# untitled.net
KiCad netlist of a schematic drawn in EAGLE
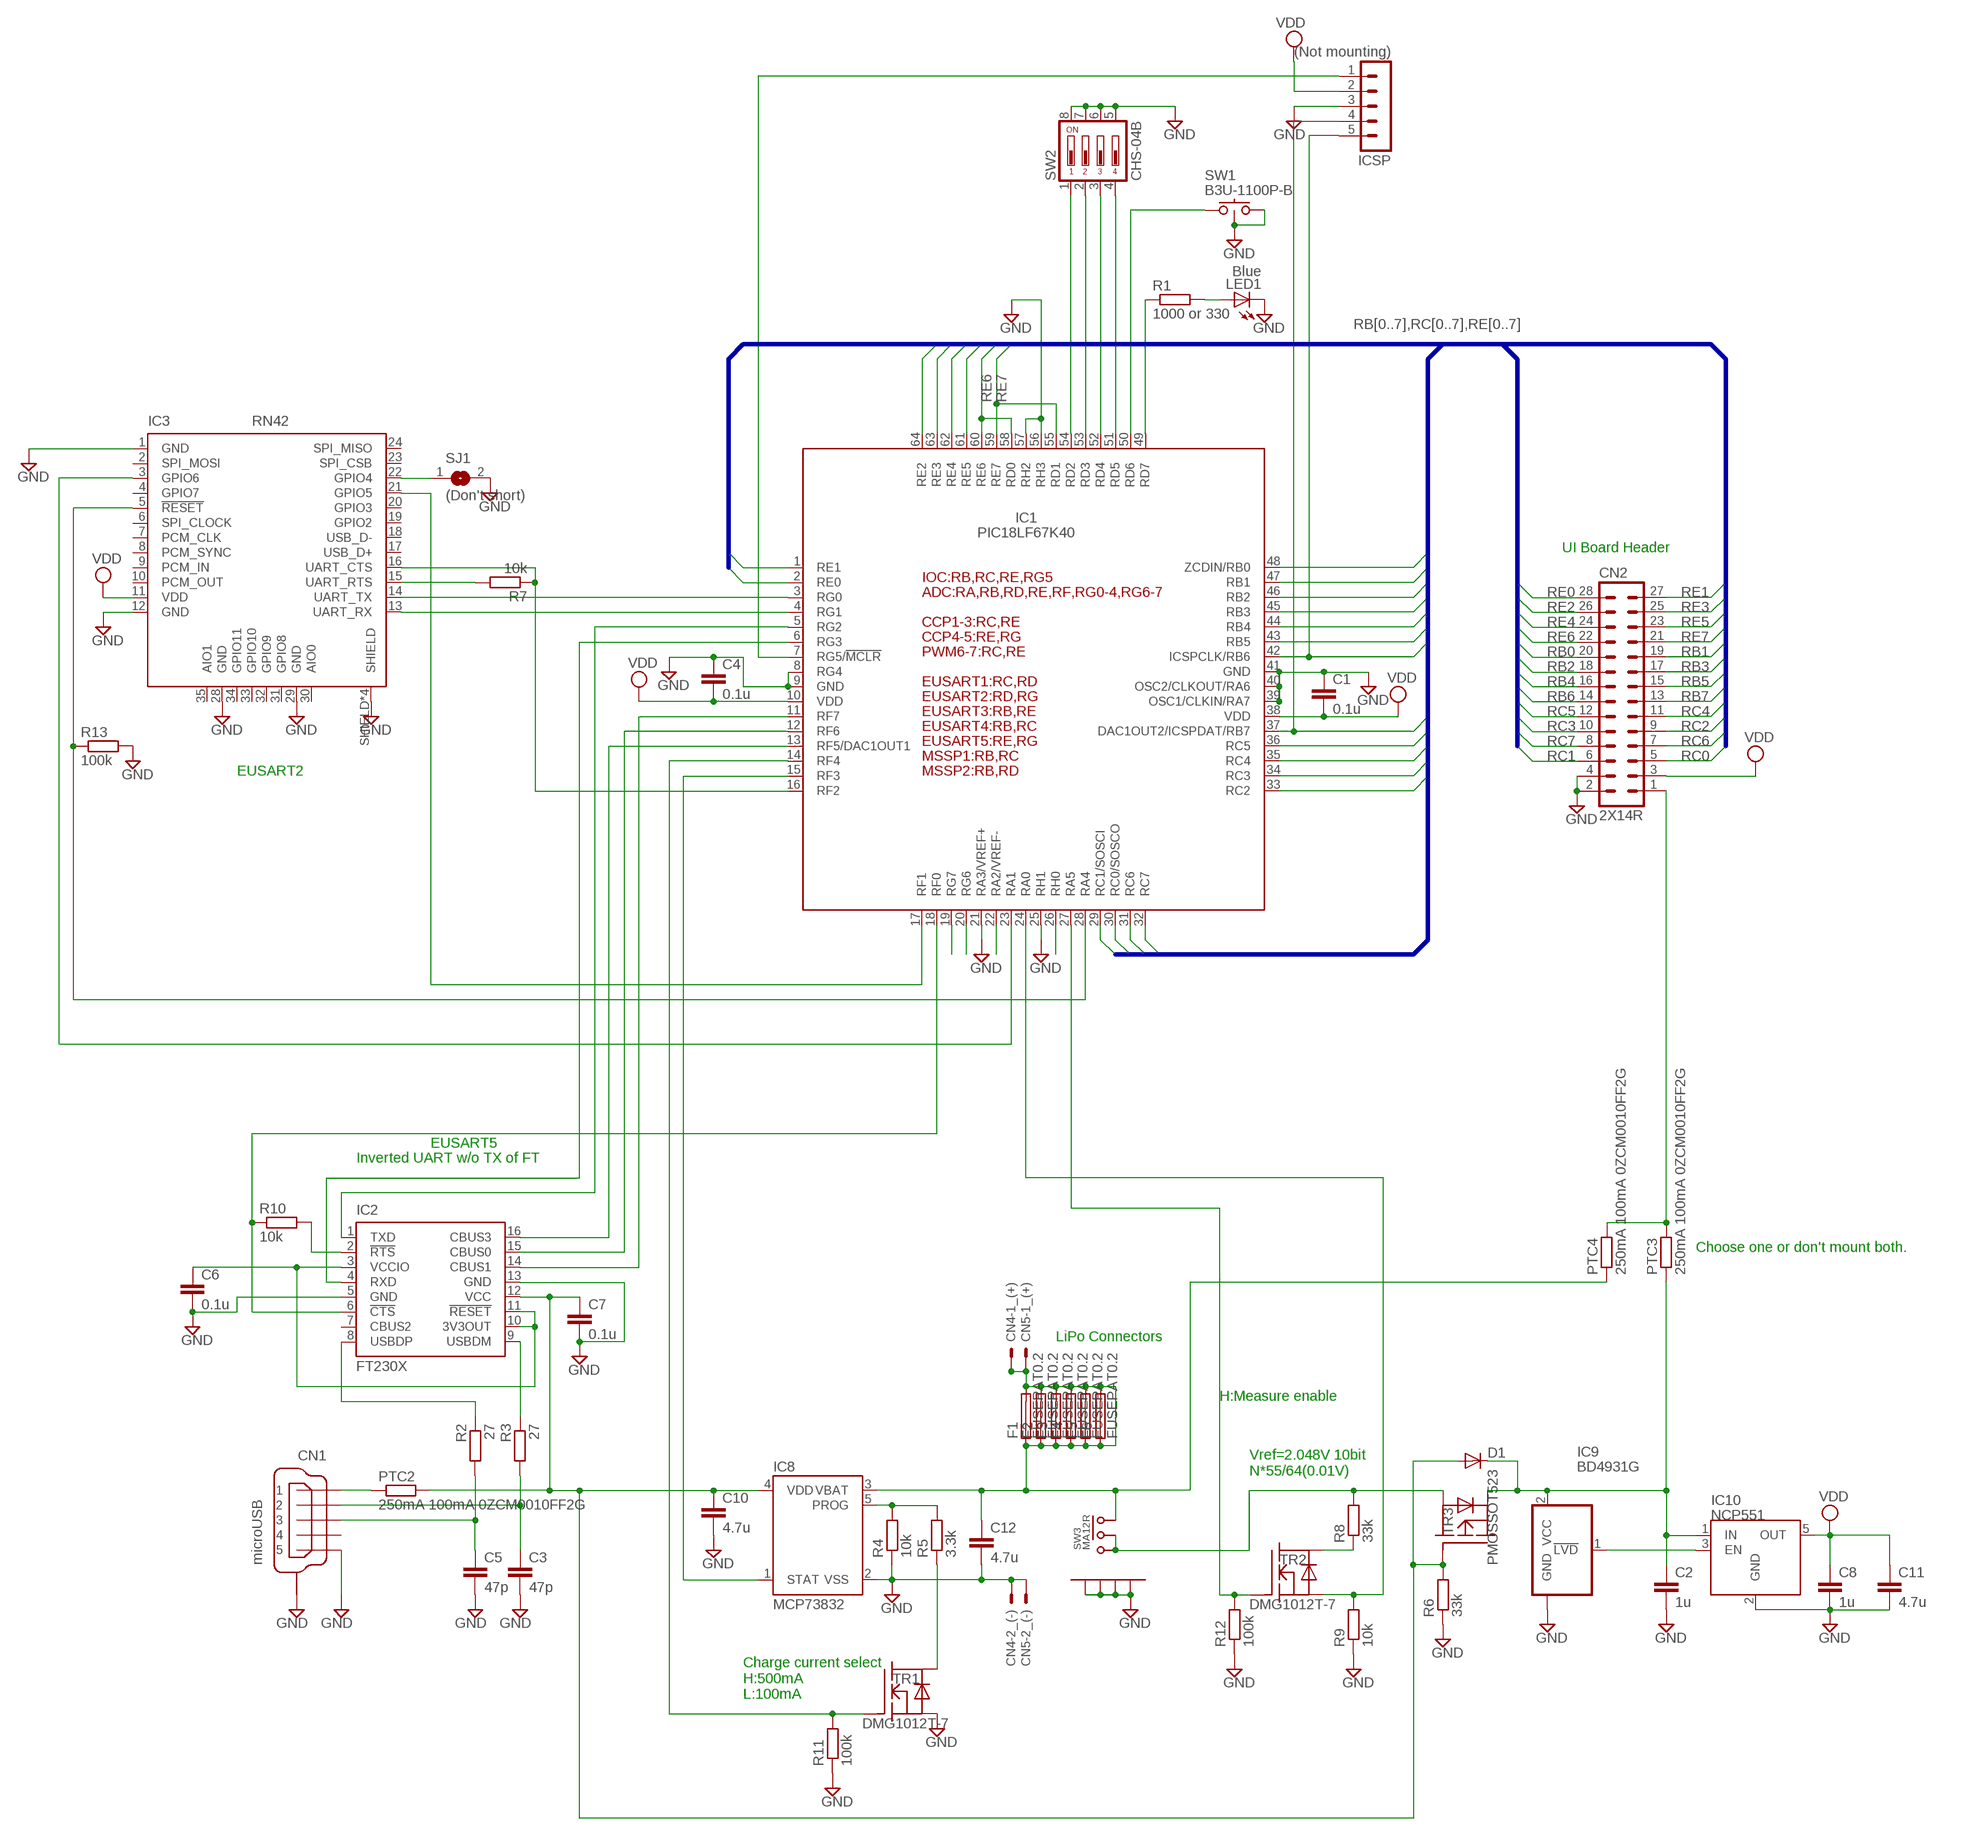
[diagram p0: schematic, sheet 1]

(export (version "E")
  (design (tool "Eeschema 10.0.6"))
  (components
    (comp (ref "C1")
      (value "0.1u")
      (footprint "eagle-import:C0402-SS")
      (libsource (lib "eagle-import") (part "C-EUC0402-SS"))
    )
    (comp (ref "C2")
      (value "1u")
      (footprint "eagle-import:C0805")
      (libsource (lib "eagle-import") (part "C-EUC0805"))
    )
    (comp (ref "C3")
      (value "47p")
      (footprint "eagle-import:C0402-SS")
      (libsource (lib "eagle-import") (part "C-EUC0402-SS"))
    )
    (comp (ref "C4")
      (value "0.1u")
      (footprint "eagle-import:C0402-SS")
      (libsource (lib "eagle-import") (part "C-EUC0402-SS"))
    )
    (comp (ref "C5")
      (value "47p")
      (footprint "eagle-import:C0402-SS")
      (libsource (lib "eagle-import") (part "C-EUC0402-SS"))
    )
    (comp (ref "C6")
      (value "0.1u")
      (footprint "eagle-import:C0402-SS")
      (libsource (lib "eagle-import") (part "C-EUC0402-SS"))
    )
    (comp (ref "C7")
      (value "0.1u")
      (footprint "eagle-import:C0402-SS")
      (libsource (lib "eagle-import") (part "C-EUC0402-SS"))
    )
    (comp (ref "C8")
      (value "1u")
      (footprint "eagle-import:C0805")
      (libsource (lib "eagle-import") (part "C-EUC0805"))
    )
    (comp (ref "C10")
      (value "4.7u")
      (footprint "eagle-import:C0805")
      (libsource (lib "eagle-import") (part "C-EUC0805"))
    )
    (comp (ref "C11")
      (value "4.7u")
      (footprint "eagle-import:C0805")
      (libsource (lib "eagle-import") (part "C-EUC0805"))
    )
    (comp (ref "C12")
      (value "4.7u")
      (footprint "eagle-import:C0805")
      (libsource (lib "eagle-import") (part "C-EUC0805"))
    )
    (comp (ref "CN1")
      (value "microUSB")
      (footprint "eagle-import:10118194-0001LF")
      (libsource (lib "eagle-import") (part "MICROUSB(10118194-0001LF)"))
    )
    (comp (ref "CN2")
      (value "2X14R")
      (footprint "eagle-import:2MM_14X2_R")
      (libsource (lib "eagle-import") (part "2X14R"))
    )
    (comp (ref "CN4")
      (value "2P_(POWER)PH_S")
      (footprint "eagle-import:PH-2_S")
      (libsource (lib "eagle-import") (part "2P_(POWER)PH_S"))
    )
    (comp (ref "CN5")
      (value "2P_(POWER)PH_S")
      (footprint "eagle-import:PH-2_S")
      (libsource (lib "eagle-import") (part "2P_(POWER)PH_S"))
    )
    (comp (ref "D1")
      (value "DIODE-VMN2")
      (footprint "eagle-import:VMN2")
      (libsource (lib "eagle-import") (part "DIODE-VMN2"))
    )
    (comp (ref "F1")
      (value "FUSEPAT0.2")
      (footprint "eagle-import:FUSE_PAT1")
      (libsource (lib "eagle-import") (part "FUSEPAT0.2"))
    )
    (comp (ref "F2")
      (value "FUSEPAT0.2")
      (footprint "eagle-import:FUSE_PAT1")
      (libsource (lib "eagle-import") (part "FUSEPAT0.2"))
    )
    (comp (ref "F3")
      (value "FUSEPAT0.2")
      (footprint "eagle-import:FUSE_PAT1")
      (libsource (lib "eagle-import") (part "FUSEPAT0.2"))
    )
    (comp (ref "F4")
      (value "FUSEPAT0.2")
      (footprint "eagle-import:FUSE_PAT1")
      (libsource (lib "eagle-import") (part "FUSEPAT0.2"))
    )
    (comp (ref "F5")
      (value "FUSEPAT0.2")
      (footprint "eagle-import:FUSE_PAT1")
      (libsource (lib "eagle-import") (part "FUSEPAT0.2"))
    )
    (comp (ref "F6")
      (value "FUSEPAT0.2")
      (footprint "eagle-import:FUSE_PAT1")
      (libsource (lib "eagle-import") (part "FUSEPAT0.2"))
    )
    (comp (ref "IC1")
      (value "PIC18LF67K40")
      (footprint "eagle-import:TQFP64-10X10")
      (libsource (lib "eagle-import") (part "PIC18F67K40"))
    )
    (comp (ref "IC2")
      (value "FT230X")
      (footprint "eagle-import:SSOP16")
      (libsource (lib "eagle-import") (part "FT230XS"))
    )
    (comp (ref "IC3")
      (value "RN42")
      (footprint "eagle-import:RN-42")
      (libsource (lib "eagle-import") (part "RN-42"))
    )
    (comp (ref "IC8")
      (value "MCP73832")
      (footprint "eagle-import:SOT23-5L")
      (libsource (lib "eagle-import") (part "MCP73831"))
    )
    (comp (ref "IC9")
      (value "BD4931G")
      (footprint "eagle-import:SOT23-5L")
      (libsource (lib "eagle-import") (part "BD48XX"))
    )
    (comp (ref "IC10")
      (value "NCP551")
      (footprint "eagle-import:SOT23-5L")
      (libsource (lib "eagle-import") (part "NCP551"))
    )
    (comp (ref "ICSP")
      (value "(Not mounting)")
      (footprint "eagle-import:MA05-1")
      (libsource (lib "eagle-import") (part "MA05-1"))
    )
    (comp (ref "LED1")
      (value "Blue")
      (footprint "eagle-import:CHIP-LED1005")
      (libsource (lib "eagle-import") (part "LED1005"))
    )
    (comp (ref "PTC2")
      (value "250mA 100mA 0ZCM0010FF2G")
      (footprint "eagle-import:R0603")
      (libsource (lib "eagle-import") (part "R-EU_R0603"))
    )
    (comp (ref "PTC3")
      (value "250mA 100mA 0ZCM0010FF2G")
      (footprint "eagle-import:R0603")
      (libsource (lib "eagle-import") (part "R-EU_R0603"))
    )
    (comp (ref "PTC4")
      (value "250mA 100mA 0ZCM0010FF2G")
      (footprint "eagle-import:R0603")
      (libsource (lib "eagle-import") (part "R-EU_R0603"))
    )
    (comp (ref "R1")
      (value "1000 or 330")
      (footprint "eagle-import:R0402-SS")
      (libsource (lib "eagle-import") (part "R-EU_R0402-SS"))
    )
    (comp (ref "R2")
      (value "27")
      (footprint "eagle-import:R0402-SS")
      (libsource (lib "eagle-import") (part "R-EU_R0402-SS"))
    )
    (comp (ref "R3")
      (value "27")
      (footprint "eagle-import:R0402-SS")
      (libsource (lib "eagle-import") (part "R-EU_R0402-SS"))
    )
    (comp (ref "R4")
      (value "10k")
      (footprint "eagle-import:R0402-SS")
      (libsource (lib "eagle-import") (part "R-EU_R0402-SS"))
    )
    (comp (ref "R5")
      (value "3.3k")
      (footprint "eagle-import:R0402-SS")
      (libsource (lib "eagle-import") (part "R-EU_R0402-SS"))
    )
    (comp (ref "R6")
      (value "33k")
      (footprint "eagle-import:R0402-SS")
      (libsource (lib "eagle-import") (part "R-EU_R0402-SS"))
    )
    (comp (ref "R7")
      (value "10k")
      (footprint "eagle-import:R0402-SS")
      (libsource (lib "eagle-import") (part "R-EU_R0402-SS"))
    )
    (comp (ref "R8")
      (value "33k")
      (footprint "eagle-import:R0402-SS")
      (libsource (lib "eagle-import") (part "R-EU_R0402-SS"))
    )
    (comp (ref "R9")
      (value "10k")
      (footprint "eagle-import:R0402-SS")
      (libsource (lib "eagle-import") (part "R-EU_R0402-SS"))
    )
    (comp (ref "R10")
      (value "10k")
      (footprint "eagle-import:R0402-SS")
      (libsource (lib "eagle-import") (part "R-EU_R0402-SS"))
    )
    (comp (ref "R11")
      (value "100k")
      (footprint "eagle-import:R0402-SS")
      (libsource (lib "eagle-import") (part "R-EU_R0402-SS"))
    )
    (comp (ref "R12")
      (value "100k")
      (footprint "eagle-import:R0402-SS")
      (libsource (lib "eagle-import") (part "R-EU_R0402-SS"))
    )
    (comp (ref "R13")
      (value "100k")
      (footprint "eagle-import:R0402-SS")
      (libsource (lib "eagle-import") (part "R-EU_R0402-SS"))
    )
    (comp (ref "SJ1")
      (value "(Don't short)")
      (footprint "eagle-import:SJ")
      (libsource (lib "eagle-import") (part "SJ"))
    )
    (comp (ref "SW1")
      (value "B3U-1100P-B")
      (footprint "eagle-import:B3U-1100P-B")
      (libsource (lib "eagle-import") (part "SW_WITH_EARTH(B3U-1100P)"))
    )
    (comp (ref "SW2")
      (value "CHS-04B")
      (footprint "eagle-import:CHS-04B")
      (libsource (lib "eagle-import") (part "CHS-04B"))
    )
    (comp (ref "SW3")
      (value "MA12R")
      (footprint "eagle-import:MA12R")
      (libsource (lib "eagle-import") (part "MA12R"))
    )
    (comp (ref "TR1")
      (value "DMG1012T-7")
      (footprint "eagle-import:SOT523")
      (libsource (lib "eagle-import") (part "NMOSSOT523"))
    )
    (comp (ref "TR2")
      (value "DMG1012T-7")
      (footprint "eagle-import:SOT523")
      (libsource (lib "eagle-import") (part "NMOSSOT523"))
    )
    (comp (ref "TR3")
      (value "PMOSSOT523")
      (footprint "eagle-import:SOT523")
      (libsource (lib "eagle-import") (part "PMOSSOT523"))
    )
  )
  (nets
    (net (code "1") (name "/RB0") (class "Default")
      (node (ref "CN2") (pin "20") (pinfunction "20_20") (pintype "passive"))
      (node (ref "IC1") (pin "48") (pinfunction "ZCDIN/RB0_48") (pintype "bidirectional"))
    )
    (net (code "2") (name "/RB1") (class "Default")
      (node (ref "CN2") (pin "19") (pinfunction "19_19") (pintype "passive"))
      (node (ref "IC1") (pin "47") (pinfunction "RB1_47") (pintype "bidirectional"))
    )
    (net (code "3") (name "/RB2") (class "Default")
      (node (ref "CN2") (pin "18") (pinfunction "18_18") (pintype "passive"))
      (node (ref "IC1") (pin "46") (pinfunction "RB2_46") (pintype "bidirectional"))
    )
    (net (code "4") (name "/RB3") (class "Default")
      (node (ref "CN2") (pin "17") (pinfunction "17_17") (pintype "passive"))
      (node (ref "IC1") (pin "45") (pinfunction "RB3_45") (pintype "bidirectional"))
    )
    (net (code "5") (name "/RB4") (class "Default")
      (node (ref "CN2") (pin "16") (pinfunction "16_16") (pintype "passive"))
      (node (ref "IC1") (pin "44") (pinfunction "RB4_44") (pintype "bidirectional"))
    )
    (net (code "6") (name "/RB5") (class "Default")
      (node (ref "CN2") (pin "15") (pinfunction "15_15") (pintype "passive"))
      (node (ref "IC1") (pin "43") (pinfunction "RB5_43") (pintype "bidirectional"))
    )
    (net (code "7") (name "/RB6") (class "Default")
      (node (ref "CN2") (pin "14") (pinfunction "14_14") (pintype "passive"))
      (node (ref "IC1") (pin "42") (pinfunction "ICSPCLK/RB6_42") (pintype "bidirectional"))
      (node (ref "ICSP") (pin "5") (pinfunction "5_5") (pintype "passive"))
    )
    (net (code "8") (name "/RB7") (class "Default")
      (node (ref "CN2") (pin "13") (pinfunction "13_13") (pintype "passive"))
      (node (ref "IC1") (pin "37") (pinfunction "DAC1OUT2/ICSPDAT/RB7_37") (pintype "bidirectional"))
      (node (ref "ICSP") (pin "4") (pinfunction "4_4") (pintype "passive"))
    )
    (net (code "9") (name "/RC0") (class "Default")
      (node (ref "CN2") (pin "5") (pinfunction "5_5") (pintype "passive"))
      (node (ref "IC1") (pin "30") (pinfunction "RC0/SOSCO_30") (pintype "bidirectional"))
    )
    (net (code "10") (name "/RC1") (class "Default")
      (node (ref "CN2") (pin "6") (pinfunction "6_6") (pintype "passive"))
      (node (ref "IC1") (pin "29") (pinfunction "RC1/SOSCI_29") (pintype "bidirectional"))
    )
    (net (code "11") (name "/RC2") (class "Default")
      (node (ref "CN2") (pin "9") (pinfunction "9_9") (pintype "passive"))
      (node (ref "IC1") (pin "33") (pinfunction "RC2_33") (pintype "bidirectional"))
    )
    (net (code "12") (name "/RC3") (class "Default")
      (node (ref "CN2") (pin "10") (pinfunction "10_10") (pintype "passive"))
      (node (ref "IC1") (pin "34") (pinfunction "RC3_34") (pintype "bidirectional"))
    )
    (net (code "13") (name "/RC4") (class "Default")
      (node (ref "CN2") (pin "11") (pinfunction "11_11") (pintype "passive"))
      (node (ref "IC1") (pin "35") (pinfunction "RC4_35") (pintype "bidirectional"))
    )
    (net (code "14") (name "/RC5") (class "Default")
      (node (ref "CN2") (pin "12") (pinfunction "12_12") (pintype "passive"))
      (node (ref "IC1") (pin "36") (pinfunction "RC5_36") (pintype "bidirectional"))
    )
    (net (code "15") (name "/RC6") (class "Default")
      (node (ref "CN2") (pin "7") (pinfunction "7_7") (pintype "passive"))
      (node (ref "IC1") (pin "31") (pinfunction "RC6_31") (pintype "bidirectional"))
    )
    (net (code "16") (name "/RC7") (class "Default")
      (node (ref "CN2") (pin "8") (pinfunction "8_8") (pintype "passive"))
      (node (ref "IC1") (pin "32") (pinfunction "RC7_32") (pintype "bidirectional"))
    )
    (net (code "17") (name "/RE0") (class "Default")
      (node (ref "CN2") (pin "28") (pinfunction "28_28") (pintype "passive"))
      (node (ref "IC1") (pin "2") (pinfunction "RE0_2") (pintype "bidirectional"))
    )
    (net (code "18") (name "/RE1") (class "Default")
      (node (ref "CN2") (pin "27") (pinfunction "27_27") (pintype "passive"))
      (node (ref "IC1") (pin "1") (pinfunction "RE1_1") (pintype "bidirectional"))
    )
    (net (code "19") (name "/RE2") (class "Default")
      (node (ref "CN2") (pin "26") (pinfunction "26_26") (pintype "passive"))
      (node (ref "IC1") (pin "64") (pinfunction "RE2_64") (pintype "bidirectional"))
    )
    (net (code "20") (name "/RE3") (class "Default")
      (node (ref "CN2") (pin "25") (pinfunction "25_25") (pintype "passive"))
      (node (ref "IC1") (pin "63") (pinfunction "RE3_63") (pintype "bidirectional"))
    )
    (net (code "21") (name "/RE4") (class "Default")
      (node (ref "CN2") (pin "24") (pinfunction "24_24") (pintype "passive"))
      (node (ref "IC1") (pin "62") (pinfunction "RE4_62") (pintype "bidirectional"))
    )
    (net (code "22") (name "/RE5") (class "Default")
      (node (ref "CN2") (pin "23") (pinfunction "23_23") (pintype "passive"))
      (node (ref "IC1") (pin "61") (pinfunction "RE5_61") (pintype "bidirectional"))
    )
    (net (code "23") (name "/RE6") (class "Default")
      (node (ref "CN2") (pin "22") (pinfunction "22_22") (pintype "passive"))
      (node (ref "IC1") (pin "58") (pinfunction "RD0_58") (pintype "bidirectional"))
      (node (ref "IC1") (pin "60") (pinfunction "RE6_60") (pintype "bidirectional"))
    )
    (net (code "24") (name "/RE7") (class "Default")
      (node (ref "CN2") (pin "21") (pinfunction "21_21") (pintype "passive"))
      (node (ref "IC1") (pin "55") (pinfunction "RD1_55") (pintype "bidirectional"))
      (node (ref "IC1") (pin "59") (pinfunction "RE7_59") (pintype "bidirectional"))
    )
    (net (code "26") (name "GND") (class "Default")
      (node (ref "C1") (pin "1") (pinfunction "1_1") (pintype "passive"))
      (node (ref "C10") (pin "2") (pinfunction "2_2") (pintype "passive"))
      (node (ref "C11") (pin "2") (pinfunction "2_2") (pintype "passive"))
      (node (ref "C12") (pin "2") (pinfunction "2_2") (pintype "passive"))
      (node (ref "C2") (pin "2") (pinfunction "2_2") (pintype "passive"))
      (node (ref "C3") (pin "2") (pinfunction "2_2") (pintype "passive"))
      (node (ref "C4") (pin "1") (pinfunction "1_1") (pintype "passive"))
      (node (ref "C5") (pin "2") (pinfunction "2_2") (pintype "passive"))
      (node (ref "C6") (pin "2") (pinfunction "2_2") (pintype "passive"))
      (node (ref "C7") (pin "2") (pinfunction "2_2") (pintype "passive"))
      (node (ref "C8") (pin "2") (pinfunction "2_2") (pintype "passive"))
      (node (ref "CN1") (pin "P$5") (pinfunction "5_P$5") (pintype "passive"))
      (node (ref "CN1") (pin "P$6") (pinfunction "S_P$6") (pintype "passive"))
      (node (ref "CN1") (pin "P$7") (pinfunction "S_P$7") (pintype "passive"))
      (node (ref "CN1") (pin "S1") (pinfunction "S_S1") (pintype "passive"))
      (node (ref "CN1") (pin "S10") (pinfunction "S_S10") (pintype "passive"))
      (node (ref "CN1") (pin "S2") (pinfunction "S_S2") (pintype "passive"))
      (node (ref "CN1") (pin "S3") (pinfunction "S_S3") (pintype "passive"))
      (node (ref "CN1") (pin "S4") (pinfunction "S_S4") (pintype "passive"))
      (node (ref "CN1") (pin "S5") (pinfunction "S_S5") (pintype "passive"))
      (node (ref "CN1") (pin "S6") (pinfunction "S_S6") (pintype "passive"))
      (node (ref "CN1") (pin "S7") (pinfunction "S_S7") (pintype "passive"))
      (node (ref "CN1") (pin "S8") (pinfunction "S_S8") (pintype "passive"))
      (node (ref "CN1") (pin "S9") (pinfunction "S_S9") (pintype "passive"))
      (node (ref "CN2") (pin "2") (pinfunction "2_2") (pintype "passive"))
      (node (ref "CN2") (pin "4") (pinfunction "4_4") (pintype "passive"))
      (node (ref "CN4") (pin "2") (pinfunction "S_2") (pintype "passive"))
      (node (ref "CN5") (pin "2") (pinfunction "S_2") (pintype "passive"))
      (node (ref "IC1") (pin "21") (pinfunction "RA3/VREF+_21") (pintype "bidirectional"))
      (node (ref "IC1") (pin "25") (pinfunction "RH1_25") (pintype "bidirectional"))
      (node (ref "IC1") (pin "39") (pinfunction "OSC1/CLKIN/RA7_39") (pintype "bidirectional"))
      (node (ref "IC1") (pin "40") (pinfunction "OSC2/CLKOUT/RA6_40") (pintype "bidirectional"))
      (node (ref "IC1") (pin "41") (pinfunction "GND_41") (pintype "power_in"))
      (node (ref "IC1") (pin "56") (pinfunction "RH3_56") (pintype "bidirectional"))
      (node (ref "IC1") (pin "57") (pinfunction "RH2_57") (pintype "bidirectional"))
      (node (ref "IC1") (pin "8") (pinfunction "RG4_8") (pintype "bidirectional"))
      (node (ref "IC1") (pin "9") (pinfunction "GND_9") (pintype "power_in"))
      (node (ref "IC10") (pin "2") (pinfunction "GND_2") (pintype "power_in"))
      (node (ref "IC2") (pin "13") (pinfunction "GND_13") (pintype "power_in"))
      (node (ref "IC2") (pin "5") (pinfunction "GND_5") (pintype "power_in"))
      (node (ref "IC3") (pin "1") (pinfunction "GND_1") (pintype "bidirectional"))
      (node (ref "IC3") (pin "12") (pinfunction "GND_12") (pintype "bidirectional"))
      (node (ref "IC3") (pin "28") (pinfunction "GND_28") (pintype "bidirectional"))
      (node (ref "IC3") (pin "29") (pinfunction "GND_29") (pintype "bidirectional"))
      (node (ref "IC3") (pin "SHIELD") (pinfunction "SHIELD_SHIELD") (pintype "bidirectional"))
      (node (ref "IC3") (pin "SHIELD@1") (pinfunction "SHIELD_SHIELD@1") (pintype "bidirectional"))
      (node (ref "IC3") (pin "SHIELD@2") (pinfunction "SHIELD_SHIELD@2") (pintype "bidirectional"))
      (node (ref "IC3") (pin "SHIELD@3") (pinfunction "SHIELD_SHIELD@3") (pintype "bidirectional"))
      (node (ref "IC8") (pin "2") (pinfunction "VSS_2") (pintype "power_in"))
      (node (ref "IC9") (pin "3") (pinfunction "GND_3") (pintype "power_in"))
      (node (ref "ICSP") (pin "3") (pinfunction "3_3") (pintype "passive"))
      (node (ref "LED1") (pin "C") (pinfunction "C_C") (pintype "passive"))
      (node (ref "R11") (pin "1") (pinfunction "1_1") (pintype "passive"))
      (node (ref "R12") (pin "1") (pinfunction "1_1") (pintype "passive"))
      (node (ref "R13") (pin "2") (pinfunction "2_2") (pintype "passive"))
      (node (ref "R4") (pin "1") (pinfunction "1_1") (pintype "passive"))
      (node (ref "R6") (pin "1") (pinfunction "1_1") (pintype "passive"))
      (node (ref "R9") (pin "1") (pinfunction "1_1") (pintype "passive"))
      (node (ref "SJ1") (pin "2") (pinfunction "2_2") (pintype "passive"))
      (node (ref "SW1") (pin "P$2") (pinfunction "P$2_P$2") (pintype "passive"))
      (node (ref "SW1") (pin "P$3") (pinfunction "P$3_P$3") (pintype "passive"))
      (node (ref "SW2") (pin "5") (pinfunction "5_5") (pintype "passive"))
      (node (ref "SW2") (pin "6") (pinfunction "6_6") (pintype "passive"))
      (node (ref "SW2") (pin "7") (pinfunction "7_7") (pintype "passive"))
      (node (ref "SW2") (pin "8") (pinfunction "8_8") (pintype "passive"))
      (node (ref "SW3") (pin "P$4") (pinfunction "P$1_P$4") (pintype "bidirectional"))
      (node (ref "SW3") (pin "P$5") (pinfunction "P$2_P$5") (pintype "bidirectional"))
      (node (ref "SW3") (pin "P$6") (pinfunction "P$3_P$6") (pintype "bidirectional"))
      (node (ref "SW3") (pin "P$7") (pinfunction "P$4_P$7") (pintype "bidirectional"))
      (node (ref "TR1") (pin "2") (pinfunction "S_2") (pintype "bidirectional"))
    )
    (net (code "27") (name "Net-(CN1-1)") (class "Default")
      (node (ref "CN1") (pin "P$1") (pinfunction "1_P$1") (pintype "passive"))
      (node (ref "PTC2") (pin "1") (pinfunction "1_1") (pintype "passive"))
    )
    (net (code "28") (name "Net-(CN1-2)") (class "Default")
      (node (ref "C3") (pin "1") (pinfunction "1_1") (pintype "passive"))
      (node (ref "CN1") (pin "P$2") (pinfunction "2_P$2") (pintype "passive"))
      (node (ref "R3") (pin "2") (pinfunction "2_2") (pintype "passive"))
    )
    (net (code "29") (name "Net-(CN1-3)") (class "Default")
      (node (ref "C5") (pin "1") (pinfunction "1_1") (pintype "passive"))
      (node (ref "CN1") (pin "P$3") (pinfunction "3_P$3") (pintype "passive"))
      (node (ref "R2") (pin "2") (pinfunction "2_2") (pintype "passive"))
    )
    (net (code "30") (name "Net-(CN2-Pad1)") (class "Default")
      (node (ref "CN2") (pin "1") (pinfunction "1_1") (pintype "passive"))
      (node (ref "PTC3") (pin "2") (pinfunction "2_2") (pintype "passive"))
      (node (ref "PTC4") (pin "2") (pinfunction "2_2") (pintype "passive"))
    )
    (net (code "31") (name "Net-(CN4A-S)") (class "Default")
      (node (ref "C12") (pin "1") (pinfunction "1_1") (pintype "passive"))
      (node (ref "CN4") (pin "1") (pinfunction "S_1") (pintype "passive"))
      (node (ref "CN5") (pin "1") (pinfunction "S_1") (pintype "passive"))
      (node (ref "F1") (pin "P$1") (pinfunction "1_P$1") (pintype "passive"))
      (node (ref "F1") (pin "P$2") (pinfunction "2_P$2") (pintype "passive"))
      (node (ref "F2") (pin "P$1") (pinfunction "1_P$1") (pintype "passive"))
      (node (ref "F2") (pin "P$2") (pinfunction "2_P$2") (pintype "passive"))
      (node (ref "F3") (pin "P$1") (pinfunction "1_P$1") (pintype "passive"))
      (node (ref "F3") (pin "P$2") (pinfunction "2_P$2") (pintype "passive"))
      (node (ref "F4") (pin "P$1") (pinfunction "1_P$1") (pintype "passive"))
      (node (ref "F4") (pin "P$2") (pinfunction "2_P$2") (pintype "passive"))
      (node (ref "F5") (pin "P$1") (pinfunction "1_P$1") (pintype "passive"))
      (node (ref "F5") (pin "P$2") (pinfunction "2_P$2") (pintype "passive"))
      (node (ref "F6") (pin "P$1") (pinfunction "1_P$1") (pintype "passive"))
      (node (ref "F6") (pin "P$2") (pinfunction "2_P$2") (pintype "passive"))
      (node (ref "IC8") (pin "3") (pinfunction "VBAT_3") (pintype "output"))
      (node (ref "PTC4") (pin "1") (pinfunction "1_1") (pintype "passive"))
      (node (ref "SW3") (pin "P$1") (pinfunction "1_P$1") (pintype "bidirectional"))
    )
    (net (code "32") (name "Net-(IC1-RA0)") (class "Default")
      (node (ref "IC1") (pin "24") (pinfunction "RA0_24") (pintype "bidirectional"))
      (node (ref "R9") (pin "2") (pinfunction "2_2") (pintype "passive"))
      (node (ref "TR2") (pin "2") (pinfunction "S_2") (pintype "bidirectional"))
    )
    (net (code "33") (name "Net-(IC1-RA1)") (class "Default")
      (node (ref "IC1") (pin "23") (pinfunction "RA1_23") (pintype "bidirectional"))
      (node (ref "IC3") (pin "3") (pinfunction "GPIO6_3") (pintype "bidirectional"))
    )
    (net (code "34") (name "Net-(IC1-RA4)") (class "Default")
      (node (ref "IC1") (pin "28") (pinfunction "RA4_28") (pintype "bidirectional"))
      (node (ref "IC3") (pin "5") (pinfunction "~{RESET}_5") (pintype "bidirectional"))
      (node (ref "R13") (pin "1") (pinfunction "1_1") (pintype "passive"))
    )
    (net (code "35") (name "Net-(IC1-RA5)") (class "Default")
      (node (ref "IC1") (pin "27") (pinfunction "RA5_27") (pintype "bidirectional"))
      (node (ref "R12") (pin "2") (pinfunction "2_2") (pintype "passive"))
      (node (ref "TR2") (pin "1") (pinfunction "G_1") (pintype "bidirectional"))
    )
    (net (code "36") (name "Net-(IC1-RD2)") (class "Default")
      (node (ref "IC1") (pin "54") (pinfunction "RD2_54") (pintype "bidirectional"))
      (node (ref "SW2") (pin "1") (pinfunction "1_1") (pintype "passive"))
    )
    (net (code "37") (name "Net-(IC1-RD3)") (class "Default")
      (node (ref "IC1") (pin "53") (pinfunction "RD3_53") (pintype "bidirectional"))
      (node (ref "SW2") (pin "2") (pinfunction "2_2") (pintype "passive"))
    )
    (net (code "38") (name "Net-(IC1-RD4)") (class "Default")
      (node (ref "IC1") (pin "52") (pinfunction "RD4_52") (pintype "bidirectional"))
      (node (ref "SW2") (pin "3") (pinfunction "3_3") (pintype "passive"))
    )
    (net (code "39") (name "Net-(IC1-RD5)") (class "Default")
      (node (ref "IC1") (pin "51") (pinfunction "RD5_51") (pintype "bidirectional"))
      (node (ref "SW2") (pin "4") (pinfunction "4_4") (pintype "passive"))
    )
    (net (code "40") (name "Net-(IC1-RD6)") (class "Default")
      (node (ref "IC1") (pin "50") (pinfunction "RD6_50") (pintype "bidirectional"))
      (node (ref "SW1") (pin "P$1") (pinfunction "P$1_P$1") (pintype "passive"))
    )
    (net (code "41") (name "Net-(IC1-RD7)") (class "Default")
      (node (ref "IC1") (pin "49") (pinfunction "RD7_49") (pintype "bidirectional"))
      (node (ref "R1") (pin "1") (pinfunction "1_1") (pintype "passive"))
    )
    (net (code "42") (name "Net-(IC1-RF0)") (class "Default")
      (node (ref "IC1") (pin "18") (pinfunction "RF0_18") (pintype "bidirectional"))
      (node (ref "IC2") (pin "6") (pinfunction "~{CTS}_6") (pintype "input"))
      (node (ref "R10") (pin "1") (pinfunction "1_1") (pintype "passive"))
    )
    (net (code "43") (name "Net-(IC1-RF1)") (class "Default")
      (node (ref "IC1") (pin "17") (pinfunction "RF1_17") (pintype "bidirectional"))
      (node (ref "IC3") (pin "21") (pinfunction "GPIO5_21") (pintype "bidirectional"))
    )
    (net (code "44") (name "Net-(IC1-RF2)") (class "Default")
      (node (ref "IC1") (pin "16") (pinfunction "RF2_16") (pintype "bidirectional"))
      (node (ref "IC3") (pin "16") (pinfunction "UART_CTS_16") (pintype "bidirectional"))
      (node (ref "R7") (pin "1") (pinfunction "1_1") (pintype "passive"))
    )
    (net (code "45") (name "Net-(IC1-RF3)") (class "Default")
      (node (ref "IC1") (pin "15") (pinfunction "RF3_15") (pintype "bidirectional"))
      (node (ref "IC8") (pin "1") (pinfunction "STAT_1") (pintype "output"))
    )
    (net (code "46") (name "Net-(IC1-RF4)") (class "Default")
      (node (ref "IC1") (pin "14") (pinfunction "RF4_14") (pintype "bidirectional"))
      (node (ref "R11") (pin "2") (pinfunction "2_2") (pintype "passive"))
      (node (ref "TR1") (pin "1") (pinfunction "G_1") (pintype "bidirectional"))
    )
    (net (code "47") (name "Net-(IC1-RF5{slash}DAC1OUT1)") (class "Default")
      (node (ref "IC1") (pin "13") (pinfunction "RF5/DAC1OUT1_13") (pintype "bidirectional"))
      (node (ref "IC2") (pin "16") (pinfunction "CBUS3_16") (pintype "bidirectional"))
    )
    (net (code "48") (name "Net-(IC1-RF6)") (class "Default")
      (node (ref "IC1") (pin "12") (pinfunction "RF6_12") (pintype "bidirectional"))
      (node (ref "IC2") (pin "15") (pinfunction "CBUS0_15") (pintype "bidirectional"))
    )
    (net (code "49") (name "Net-(IC1-RF7)") (class "Default")
      (node (ref "IC1") (pin "11") (pinfunction "RF7_11") (pintype "bidirectional"))
      (node (ref "IC2") (pin "14") (pinfunction "CBUS1_14") (pintype "bidirectional"))
    )
    (net (code "50") (name "Net-(IC1-RG0)") (class "Default")
      (node (ref "IC1") (pin "3") (pinfunction "RG0_3") (pintype "bidirectional"))
      (node (ref "IC3") (pin "14") (pinfunction "UART_TX_14") (pintype "bidirectional"))
    )
    (net (code "51") (name "Net-(IC1-RG1)") (class "Default")
      (node (ref "IC1") (pin "4") (pinfunction "RG1_4") (pintype "bidirectional"))
      (node (ref "IC3") (pin "13") (pinfunction "UART_RX_13") (pintype "bidirectional"))
    )
    (net (code "52") (name "Net-(IC1-RG2)") (class "Default")
      (node (ref "IC1") (pin "5") (pinfunction "RG2_5") (pintype "bidirectional"))
      (node (ref "IC2") (pin "1") (pinfunction "TXD_1") (pintype "output"))
    )
    (net (code "53") (name "Net-(IC1-RG3)") (class "Default")
      (node (ref "IC1") (pin "6") (pinfunction "RG3_6") (pintype "bidirectional"))
      (node (ref "IC2") (pin "4") (pinfunction "RXD_4") (pintype "input"))
    )
    (net (code "54") (name "Net-(IC1-RG5{slash}~{MCLR})") (class "Default")
      (node (ref "IC1") (pin "7") (pinfunction "RG5/~{MCLR}_7") (pintype "input"))
      (node (ref "ICSP") (pin "1") (pinfunction "1_1") (pintype "passive"))
    )
    (net (code "55") (name "Net-(IC2-3V3OUT)") (class "Default")
      (node (ref "C6") (pin "1") (pinfunction "1_1") (pintype "passive"))
      (node (ref "IC2") (pin "10") (pinfunction "3V3OUT_10") (pintype "output"))
      (node (ref "IC2") (pin "11") (pinfunction "~{RESET}_11") (pintype "input"))
      (node (ref "IC2") (pin "3") (pinfunction "VCCIO_3") (pintype "power_in"))
    )
    (net (code "56") (name "Net-(IC2-USBDM)") (class "Default")
      (node (ref "IC2") (pin "9") (pinfunction "USBDM_9") (pintype "input"))
      (node (ref "R3") (pin "1") (pinfunction "1_1") (pintype "passive"))
    )
    (net (code "57") (name "Net-(IC2-USBDP)") (class "Default")
      (node (ref "IC2") (pin "8") (pinfunction "USBDP_8") (pintype "input"))
      (node (ref "R2") (pin "1") (pinfunction "1_1") (pintype "passive"))
    )
    (net (code "58") (name "Net-(IC2-VCC)") (class "Default")
      (node (ref "C10") (pin "1") (pinfunction "1_1") (pintype "passive"))
      (node (ref "C7") (pin "1") (pinfunction "1_1") (pintype "passive"))
      (node (ref "D1") (pin "A") (pinfunction "A_A") (pintype "passive"))
      (node (ref "IC2") (pin "12") (pinfunction "VCC_12") (pintype "power_in"))
      (node (ref "IC8") (pin "4") (pinfunction "VDD_4") (pintype "power_in"))
      (node (ref "PTC2") (pin "2") (pinfunction "2_2") (pintype "passive"))
      (node (ref "R6") (pin "2") (pinfunction "2_2") (pintype "passive"))
      (node (ref "TR3") (pin "1") (pinfunction "G_1") (pintype "bidirectional"))
    )
    (net (code "59") (name "Net-(IC2-~{RTS})") (class "Default")
      (node (ref "IC2") (pin "2") (pinfunction "~{RTS}_2") (pintype "output"))
      (node (ref "R10") (pin "2") (pinfunction "2_2") (pintype "passive"))
    )
    (net (code "60") (name "Net-(IC3-GPIO4)") (class "Default")
      (node (ref "IC3") (pin "22") (pinfunction "GPIO4_22") (pintype "bidirectional"))
      (node (ref "SJ1") (pin "1") (pinfunction "1_1") (pintype "passive"))
    )
    (net (code "61") (name "Net-(IC3-UART_RTS)") (class "Default")
      (node (ref "IC3") (pin "15") (pinfunction "UART_RTS_15") (pintype "bidirectional"))
      (node (ref "R7") (pin "2") (pinfunction "2_2") (pintype "passive"))
    )
    (net (code "62") (name "Net-(IC8-PROG)") (class "Default")
      (node (ref "IC8") (pin "5") (pinfunction "PROG_5") (pintype "input"))
      (node (ref "R4") (pin "2") (pinfunction "2_2") (pintype "passive"))
      (node (ref "R5") (pin "2") (pinfunction "2_2") (pintype "passive"))
    )
    (net (code "63") (name "Net-(IC10-EN)") (class "Default")
      (node (ref "IC10") (pin "3") (pinfunction "EN_3") (pintype "input"))
      (node (ref "IC9") (pin "1") (pinfunction "~{LVD}_1") (pintype "output"))
    )
    (net (code "64") (name "Net-(IC10-IN)") (class "Default")
      (node (ref "C2") (pin "1") (pinfunction "1_1") (pintype "passive"))
      (node (ref "D1") (pin "C") (pinfunction "C_C") (pintype "passive"))
      (node (ref "IC10") (pin "1") (pinfunction "IN_1") (pintype "power_in"))
      (node (ref "IC9") (pin "2") (pinfunction "VCC_2") (pintype "power_in"))
      (node (ref "PTC3") (pin "1") (pinfunction "1_1") (pintype "passive"))
      (node (ref "TR3") (pin "2") (pinfunction "S_2") (pintype "bidirectional"))
    )
    (net (code "65") (name "Net-(LED1-PadA)") (class "Default")
      (node (ref "LED1") (pin "A") (pinfunction "A_A") (pintype "passive"))
      (node (ref "R1") (pin "2") (pinfunction "2_2") (pintype "passive"))
    )
    (net (code "66") (name "Net-(SW3-2)") (class "Default")
      (node (ref "R8") (pin "2") (pinfunction "2_2") (pintype "passive"))
      (node (ref "SW3") (pin "P$2") (pinfunction "2_P$2") (pintype "bidirectional"))
      (node (ref "SW3") (pin "P$3") (pinfunction "3_P$3") (pintype "bidirectional"))
      (node (ref "TR3") (pin "3") (pinfunction "D_3") (pintype "bidirectional"))
    )
    (net (code "67") (name "Net-(TR1-D)") (class "Default")
      (node (ref "R5") (pin "1") (pinfunction "1_1") (pintype "passive"))
      (node (ref "TR1") (pin "3") (pinfunction "D_3") (pintype "bidirectional"))
    )
    (net (code "68") (name "Net-(TR2-D)") (class "Default")
      (node (ref "R8") (pin "1") (pinfunction "1_1") (pintype "passive"))
      (node (ref "TR2") (pin "3") (pinfunction "D_3") (pintype "bidirectional"))
    )
    (net (code "69") (name "VDD") (class "Default")
      (node (ref "C1") (pin "2") (pinfunction "2_2") (pintype "passive"))
      (node (ref "C11") (pin "1") (pinfunction "1_1") (pintype "passive"))
      (node (ref "C4") (pin "2") (pinfunction "2_2") (pintype "passive"))
      (node (ref "C8") (pin "1") (pinfunction "1_1") (pintype "passive"))
      (node (ref "CN2") (pin "3") (pinfunction "3_3") (pintype "passive"))
      (node (ref "IC1") (pin "10") (pinfunction "VDD_10") (pintype "power_in"))
      (node (ref "IC1") (pin "38") (pinfunction "VDD_38") (pintype "power_in"))
      (node (ref "IC10") (pin "5") (pinfunction "OUT_5") (pintype "output"))
      (node (ref "IC3") (pin "11") (pinfunction "VDD_11") (pintype "bidirectional"))
      (node (ref "ICSP") (pin "2") (pinfunction "2_2") (pintype "passive"))
    )
    (net (code "70") (name "unconnected-(CN1-4-PadP$4)") (class "Default")
      (node (ref "CN1") (pin "P$4") (pinfunction "4_P$4") (pintype "passive"))
    )
    (net (code "71") (name "unconnected-(IC1-RA2{slash}VREF--Pad22)") (class "Default")
      (node (ref "IC1") (pin "22") (pinfunction "RA2/VREF-_22") (pintype "bidirectional"))
    )
    (net (code "72") (name "unconnected-(IC1-RG6-Pad20)") (class "Default")
      (node (ref "IC1") (pin "20") (pinfunction "RG6_20") (pintype "bidirectional"))
    )
    (net (code "73") (name "unconnected-(IC1-RG7-Pad19)") (class "Default")
      (node (ref "IC1") (pin "19") (pinfunction "RG7_19") (pintype "bidirectional"))
    )
    (net (code "74") (name "unconnected-(IC1-RH0-Pad26)") (class "Default")
      (node (ref "IC1") (pin "26") (pinfunction "RH0_26") (pintype "bidirectional"))
    )
    (net (code "75") (name "unconnected-(IC2-CBUS2-Pad7)") (class "Default")
      (node (ref "IC2") (pin "7") (pinfunction "CBUS2_7") (pintype "bidirectional"))
    )
    (net (code "76") (name "unconnected-(IC3-AIO0-Pad30)") (class "Default")
      (node (ref "IC3") (pin "30") (pinfunction "AIO0_30") (pintype "bidirectional"))
    )
    (net (code "77") (name "unconnected-(IC3-AIO1-Pad35)") (class "Default")
      (node (ref "IC3") (pin "35") (pinfunction "AIO1_35") (pintype "bidirectional"))
    )
    (net (code "78") (name "unconnected-(IC3-GPIO2-Pad19)") (class "Default")
      (node (ref "IC3") (pin "19") (pinfunction "GPIO2_19") (pintype "bidirectional"))
    )
    (net (code "79") (name "unconnected-(IC3-GPIO3-Pad20)") (class "Default")
      (node (ref "IC3") (pin "20") (pinfunction "GPIO3_20") (pintype "bidirectional"))
    )
    (net (code "80") (name "unconnected-(IC3-GPIO7-Pad4)") (class "Default")
      (node (ref "IC3") (pin "4") (pinfunction "GPIO7_4") (pintype "bidirectional"))
    )
    (net (code "81") (name "unconnected-(IC3-GPIO8-Pad31)") (class "Default")
      (node (ref "IC3") (pin "31") (pinfunction "GPIO8_31") (pintype "bidirectional"))
    )
    (net (code "82") (name "unconnected-(IC3-GPIO9-Pad32)") (class "Default")
      (node (ref "IC3") (pin "32") (pinfunction "GPIO9_32") (pintype "bidirectional"))
    )
    (net (code "83") (name "unconnected-(IC3-GPIO10-Pad33)") (class "Default")
      (node (ref "IC3") (pin "33") (pinfunction "GPIO10_33") (pintype "bidirectional"))
    )
    (net (code "84") (name "unconnected-(IC3-GPIO11-Pad34)") (class "Default")
      (node (ref "IC3") (pin "34") (pinfunction "GPIO11_34") (pintype "bidirectional"))
    )
    (net (code "85") (name "unconnected-(IC3-PCM_CLK-Pad7)") (class "Default")
      (node (ref "IC3") (pin "7") (pinfunction "PCM_CLK_7") (pintype "bidirectional"))
    )
    (net (code "86") (name "unconnected-(IC3-PCM_IN-Pad9)") (class "Default")
      (node (ref "IC3") (pin "9") (pinfunction "PCM_IN_9") (pintype "bidirectional"))
    )
    (net (code "87") (name "unconnected-(IC3-PCM_OUT-Pad10)") (class "Default")
      (node (ref "IC3") (pin "10") (pinfunction "PCM_OUT_10") (pintype "bidirectional"))
    )
    (net (code "88") (name "unconnected-(IC3-PCM_SYNC-Pad8)") (class "Default")
      (node (ref "IC3") (pin "8") (pinfunction "PCM_SYNC_8") (pintype "bidirectional"))
    )
    (net (code "89") (name "unconnected-(IC3-SPI_CLOCK-Pad6)") (class "Default")
      (node (ref "IC3") (pin "6") (pinfunction "SPI_CLOCK_6") (pintype "bidirectional"))
    )
    (net (code "90") (name "unconnected-(IC3-SPI_CSB-Pad23)") (class "Default")
      (node (ref "IC3") (pin "23") (pinfunction "SPI_CSB_23") (pintype "bidirectional"))
    )
    (net (code "91") (name "unconnected-(IC3-SPI_MISO-Pad24)") (class "Default")
      (node (ref "IC3") (pin "24") (pinfunction "SPI_MISO_24") (pintype "bidirectional"))
    )
    (net (code "92") (name "unconnected-(IC3-SPI_MOSI-Pad2)") (class "Default")
      (node (ref "IC3") (pin "2") (pinfunction "SPI_MOSI_2") (pintype "bidirectional"))
    )
    (net (code "93") (name "unconnected-(IC3-USB_D+-Pad17)") (class "Default")
      (node (ref "IC3") (pin "17") (pinfunction "USB_D+_17") (pintype "bidirectional"))
    )
    (net (code "94") (name "unconnected-(IC3-USB_D--Pad18)") (class "Default")
      (node (ref "IC3") (pin "18") (pinfunction "USB_D-_18") (pintype "bidirectional"))
    )
  )
)
